# WMR_Sheet.net
KiCad netlist of a schematic drawn in Altium Designer
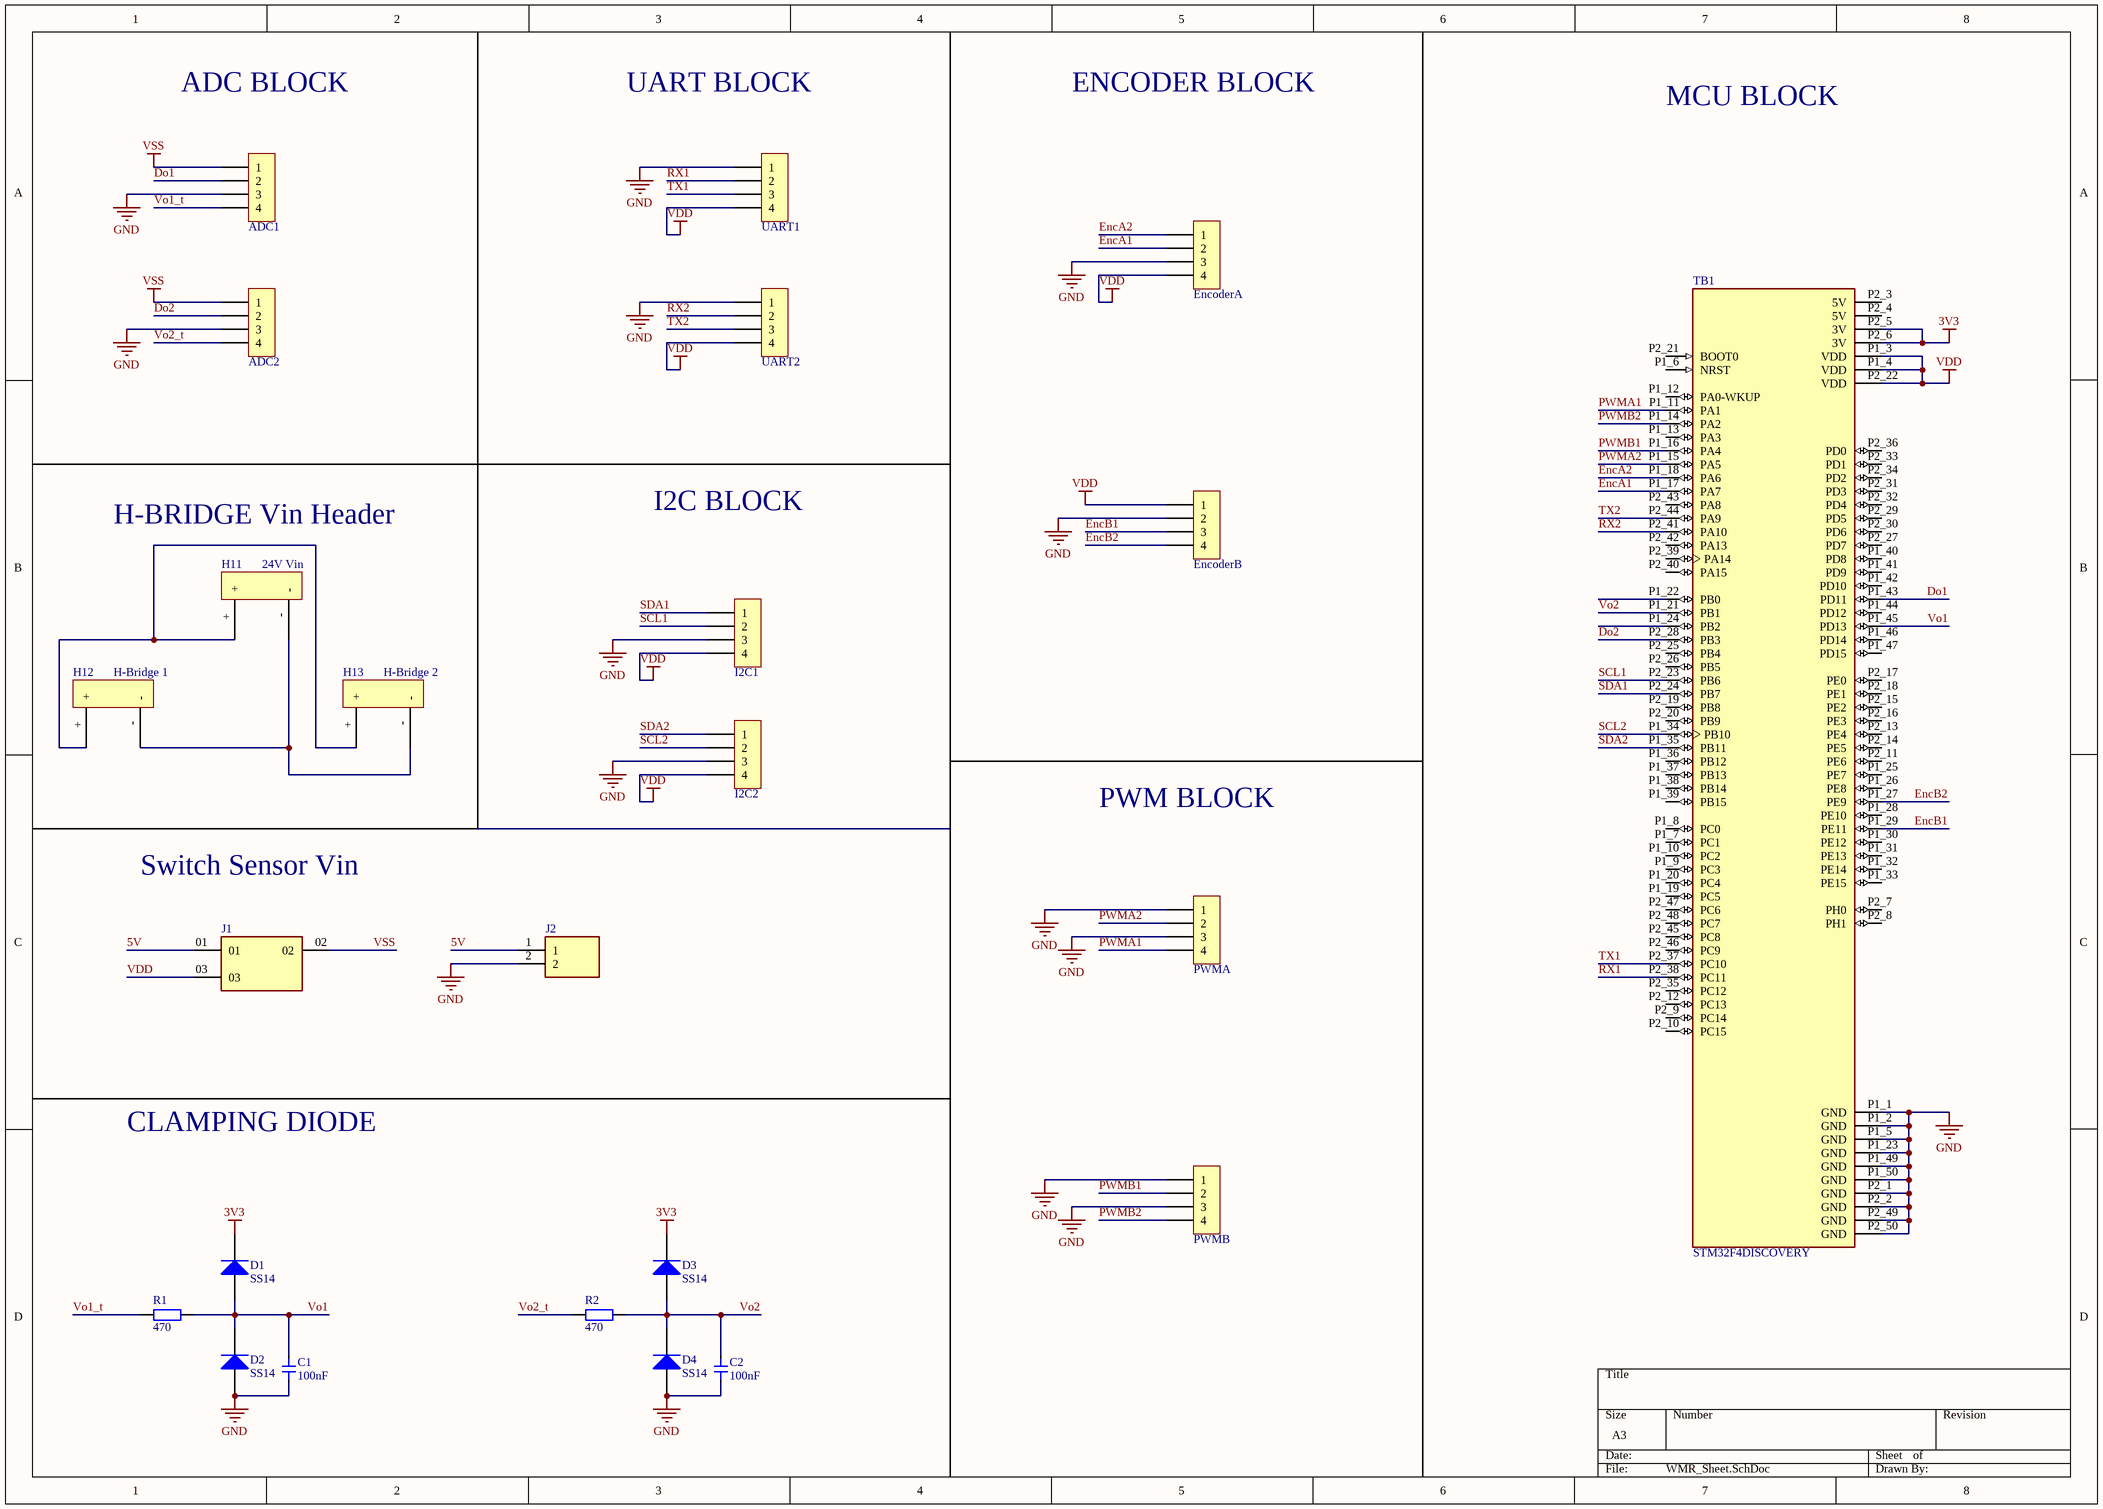
[diagram p0: WMR_Sheet.SchDoc]

(export (version "E")
  (design (tool "Eeschema 10.0.6"))
  (components
    (comp (ref "C1")
      (value "100nF")
      (footprint "Cap 1206")
      (description "Capacitor SMD 1206")
      (libsource (lib "Altium_Lib_by_KhueNguyenCreator") (part "Cap 1206"))
    )
    (comp (ref "C2")
      (value "100nF")
      (footprint "Cap 1206")
      (description "Capacitor SMD 1206")
      (libsource (lib "Altium_Lib_by_KhueNguyenCreator") (part "Cap 1206"))
    )
    (comp (ref "D1")
      (value "SS14")
      (footprint "DIODE SMA")
      (description "Dán")
      (libsource (lib "Altium_Lib_by_KhueNguyenCreator") (part "Diode SS14 ( 1N5819)"))
    )
    (comp (ref "D2")
      (value "SS14")
      (footprint "DIODE SMA")
      (description "Dán")
      (libsource (lib "Altium_Lib_by_KhueNguyenCreator") (part "Diode SS14 ( 1N5819)"))
    )
    (comp (ref "D3")
      (value "SS14")
      (footprint "DIODE SMA")
      (description "Dán")
      (libsource (lib "Altium_Lib_by_KhueNguyenCreator") (part "Diode SS14 ( 1N5819)"))
    )
    (comp (ref "D4")
      (value "SS14")
      (footprint "DIODE SMA")
      (description "Dán")
      (libsource (lib "Altium_Lib_by_KhueNguyenCreator") (part "Diode SS14 ( 1N5819)"))
    )
    (comp (ref "H1")
      (value "EncoderA")
      (footprint "XH2.54M-4")
      (description "Cắm")
      (libsource (lib "Altium_Lib_by_KhueNguyenCreator") (part "Header 4P 2.54 Duc Thang"))
    )
    (comp (ref "H2")
      (value "EncoderB")
      (footprint "XH2.54M-4")
      (description "Cắm")
      (libsource (lib "Altium_Lib_by_KhueNguyenCreator") (part "Header 4P 2.54 Duc Thang"))
    )
    (comp (ref "H3")
      (value "PWMA")
      (footprint "XH2.54M-4")
      (description "Cắm")
      (libsource (lib "Altium_Lib_by_KhueNguyenCreator") (part "Header 4P 2.54 Duc Thang"))
    )
    (comp (ref "H4")
      (value "PWMB")
      (footprint "XH2.54M-4")
      (description "Cắm")
      (libsource (lib "Altium_Lib_by_KhueNguyenCreator") (part "Header 4P 2.54 Duc Thang"))
    )
    (comp (ref "H5")
      (value "UART1")
      (footprint "XH2.54M-4")
      (description "Cắm")
      (libsource (lib "Altium_Lib_by_KhueNguyenCreator") (part "Header 4P 2.54 Duc Thang"))
    )
    (comp (ref "H6")
      (value "UART2")
      (footprint "XH2.54M-4")
      (description "Cắm")
      (libsource (lib "Altium_Lib_by_KhueNguyenCreator") (part "Header 4P 2.54 Duc Thang"))
    )
    (comp (ref "H7")
      (value "I2C1")
      (footprint "XH2.54M-4")
      (description "Cắm")
      (libsource (lib "Altium_Lib_by_KhueNguyenCreator") (part "Header 4P 2.54 Duc Thang"))
    )
    (comp (ref "H8")
      (value "I2C2")
      (footprint "XH2.54M-4")
      (description "Cắm")
      (libsource (lib "Altium_Lib_by_KhueNguyenCreator") (part "Header 4P 2.54 Duc Thang"))
    )
    (comp (ref "H9")
      (value "ADC1")
      (footprint "XH2.54M-4")
      (description "Cắm")
      (libsource (lib "Altium_Lib_by_KhueNguyenCreator") (part "Header 4P 2.54 Duc Thang"))
    )
    (comp (ref "H10")
      (value "ADC2")
      (footprint "XH2.54M-4")
      (description "Cắm")
      (libsource (lib "Altium_Lib_by_KhueNguyenCreator") (part "Header 4P 2.54 Duc Thang"))
    )
    (comp (ref "H11")
      (value "24V Vin")
      (footprint "barrier_terminal")
      (libsource (lib "BaoNguyenLib") (part "Barrier Terminal"))
    )
    (comp (ref "H12")
      (value "H-Bridge 1")
      (footprint "barrier_terminal")
      (libsource (lib "BaoNguyenLib") (part "Barrier Terminal"))
    )
    (comp (ref "H13")
      (value "H-Bridge 2")
      (footprint "barrier_terminal")
      (libsource (lib "BaoNguyenLib") (part "Barrier Terminal"))
    )
    (comp (ref "J1")
      (value "~")
      (footprint "SAMTEC_TSW-101-07-G-T-LL")
      (fields (field (name "MP") "TSW-101-07-G-T-LL"))
      (libsource (lib "Header3Pin") (part "TSW-101-07-G-T-LL"))
    )
    (comp (ref "J2")
      (value "~")
      (footprint "MULTICOMP_MC000048")
      (fields (field (name "MF") "Multicomp") (field (name "MP") "MC000048"))
      (libsource (lib "terminal2P") (part "MC000048"))
    )
    (comp (ref "R1")
      (value "470")
      (footprint "tro smd 1206")
      (description "Dán")
      (libsource (lib "Altium_Lib_by_KhueNguyenCreator") (part "Tro 1206 1% 470k"))
    )
    (comp (ref "R2")
      (value "470")
      (footprint "tro smd 1206")
      (description "Dán")
      (libsource (lib "Altium_Lib_by_KhueNguyenCreator") (part "Tro 1206 1% 470k"))
    )
    (comp (ref "TB1")
      (value "STM32F4DISCOVERY")
      (footprint "MODULE_STM32F4DISCOVERY")
      (description "Development kit: ARM ST; pin strips, pin header; No.of")
      (libsource (lib "STM32F4DISCOVERY") (part "STM32F4DISCOVERY"))
    )
  )
  (nets
    (net (code "1") (name "/5V") (class "Default")
      (node (ref "J1") (pin "01") (pinfunction "01_01") (pintype "passive"))
      (node (ref "J2") (pin "1") (pinfunction "1_1") (pintype "passive"))
    )
    (net (code "2") (name "/Do1") (class "Default")
      (node (ref "H9") (pin "2") (pinfunction "2_2") (pintype "passive"))
      (node (ref "TB1") (pin "P1_43") (pinfunction "PD11_P1_43") (pintype "bidirectional"))
    )
    (net (code "3") (name "/Do2") (class "Default")
      (node (ref "H10") (pin "2") (pinfunction "2_2") (pintype "passive"))
      (node (ref "TB1") (pin "P2_28") (pinfunction "PB3_P2_28") (pintype "bidirectional"))
    )
    (net (code "4") (name "/EncA1") (class "Default")
      (node (ref "H1") (pin "2") (pinfunction "2_2") (pintype "passive"))
      (node (ref "TB1") (pin "P1_17") (pinfunction "PA7_P1_17") (pintype "bidirectional"))
    )
    (net (code "5") (name "/EncA2") (class "Default")
      (node (ref "H1") (pin "1") (pinfunction "1_1") (pintype "passive"))
      (node (ref "TB1") (pin "P1_18") (pinfunction "PA6_P1_18") (pintype "bidirectional"))
    )
    (net (code "6") (name "/EncB1") (class "Default")
      (node (ref "H2") (pin "3") (pinfunction "3_3") (pintype "passive"))
      (node (ref "TB1") (pin "P1_29") (pinfunction "PE11_P1_29") (pintype "bidirectional"))
    )
    (net (code "7") (name "/EncB2") (class "Default")
      (node (ref "H2") (pin "4") (pinfunction "4_4") (pintype "passive"))
      (node (ref "TB1") (pin "P1_27") (pinfunction "PE9_P1_27") (pintype "bidirectional"))
    )
    (net (code "8") (name "/PWMA1") (class "Default")
      (node (ref "H3") (pin "4") (pinfunction "4_4") (pintype "passive"))
      (node (ref "TB1") (pin "P1_11") (pinfunction "PA1_P1_11") (pintype "bidirectional"))
    )
    (net (code "9") (name "/PWMA2") (class "Default")
      (node (ref "H3") (pin "2") (pinfunction "2_2") (pintype "passive"))
      (node (ref "TB1") (pin "P1_15") (pinfunction "PA5_P1_15") (pintype "bidirectional"))
    )
    (net (code "10") (name "/PWMB1") (class "Default")
      (node (ref "H4") (pin "2") (pinfunction "2_2") (pintype "passive"))
      (node (ref "TB1") (pin "P1_16") (pinfunction "PA4_P1_16") (pintype "bidirectional"))
    )
    (net (code "11") (name "/PWMB2") (class "Default")
      (node (ref "H4") (pin "4") (pinfunction "4_4") (pintype "passive"))
      (node (ref "TB1") (pin "P1_14") (pinfunction "PA2_P1_14") (pintype "bidirectional"))
    )
    (net (code "12") (name "/RX1") (class "Default")
      (node (ref "H5") (pin "2") (pinfunction "2_2") (pintype "passive"))
      (node (ref "TB1") (pin "P2_38") (pinfunction "PC11_P2_38") (pintype "bidirectional"))
    )
    (net (code "13") (name "/RX2") (class "Default")
      (node (ref "H6") (pin "2") (pinfunction "2_2") (pintype "passive"))
      (node (ref "TB1") (pin "P2_41") (pinfunction "PA10_P2_41") (pintype "bidirectional"))
    )
    (net (code "14") (name "/SCL1") (class "Default")
      (node (ref "H7") (pin "2") (pinfunction "2_2") (pintype "passive"))
      (node (ref "TB1") (pin "P2_23") (pinfunction "PB6_P2_23") (pintype "bidirectional"))
    )
    (net (code "15") (name "/SCL2") (class "Default")
      (node (ref "H8") (pin "2") (pinfunction "2_2") (pintype "passive"))
      (node (ref "TB1") (pin "P1_34") (pinfunction "PB10_P1_34") (pintype "bidirectional"))
    )
    (net (code "16") (name "/SDA1") (class "Default")
      (node (ref "H7") (pin "1") (pinfunction "1_1") (pintype "passive"))
      (node (ref "TB1") (pin "P2_24") (pinfunction "PB7_P2_24") (pintype "bidirectional"))
    )
    (net (code "17") (name "/SDA2") (class "Default")
      (node (ref "H8") (pin "1") (pinfunction "1_1") (pintype "passive"))
      (node (ref "TB1") (pin "P1_35") (pinfunction "PB11_P1_35") (pintype "bidirectional"))
    )
    (net (code "18") (name "/TX1") (class "Default")
      (node (ref "H5") (pin "3") (pinfunction "3_3") (pintype "passive"))
      (node (ref "TB1") (pin "P2_37") (pinfunction "PC10_P2_37") (pintype "bidirectional"))
    )
    (net (code "19") (name "/TX2") (class "Default")
      (node (ref "H6") (pin "3") (pinfunction "3_3") (pintype "passive"))
      (node (ref "TB1") (pin "P2_44") (pinfunction "PA9_P2_44") (pintype "bidirectional"))
    )
    (net (code "20") (name "/Vo1") (class "Default")
      (node (ref "C1") (pin "1") (pinfunction "1_1") (pintype "passive"))
      (node (ref "D1") (pin "1") (pinfunction "A_1") (pintype "passive"))
      (node (ref "D2") (pin "2") (pinfunction "K_2") (pintype "passive"))
      (node (ref "R1") (pin "2") (pinfunction "2_2") (pintype "passive"))
      (node (ref "TB1") (pin "P1_45") (pinfunction "PD13_P1_45") (pintype "bidirectional"))
    )
    (net (code "21") (name "/Vo1_t") (class "Default")
      (node (ref "H9") (pin "4") (pinfunction "4_4") (pintype "passive"))
      (node (ref "R1") (pin "1") (pinfunction "1_1") (pintype "passive"))
    )
    (net (code "22") (name "/Vo2") (class "Default")
      (node (ref "C2") (pin "1") (pinfunction "1_1") (pintype "passive"))
      (node (ref "D3") (pin "1") (pinfunction "A_1") (pintype "passive"))
      (node (ref "D4") (pin "2") (pinfunction "K_2") (pintype "passive"))
      (node (ref "R2") (pin "2") (pinfunction "2_2") (pintype "passive"))
      (node (ref "TB1") (pin "P1_21") (pinfunction "PB1_P1_21") (pintype "bidirectional"))
    )
    (net (code "23") (name "/Vo2_t") (class "Default")
      (node (ref "H10") (pin "4") (pinfunction "4_4") (pintype "passive"))
      (node (ref "R2") (pin "1") (pinfunction "1_1") (pintype "passive"))
    )
    (net (code "24") (name "3V3") (class "Default")
      (node (ref "D1") (pin "2") (pinfunction "K_2") (pintype "passive"))
      (node (ref "D3") (pin "2") (pinfunction "K_2") (pintype "passive"))
      (node (ref "TB1") (pin "P2_5") (pinfunction "3V_P2_5") (pintype "power_in"))
      (node (ref "TB1") (pin "P2_6") (pinfunction "3V_P2_6") (pintype "power_in"))
    )
    (net (code "25") (name "GND") (class "Default")
      (node (ref "C1") (pin "2") (pinfunction "2_2") (pintype "passive"))
      (node (ref "C2") (pin "2") (pinfunction "2_2") (pintype "passive"))
      (node (ref "D2") (pin "1") (pinfunction "A_1") (pintype "passive"))
      (node (ref "D4") (pin "1") (pinfunction "A_1") (pintype "passive"))
      (node (ref "H1") (pin "3") (pinfunction "3_3") (pintype "passive"))
      (node (ref "H10") (pin "3") (pinfunction "3_3") (pintype "passive"))
      (node (ref "H2") (pin "2") (pinfunction "2_2") (pintype "passive"))
      (node (ref "H3") (pin "1") (pinfunction "1_1") (pintype "passive"))
      (node (ref "H3") (pin "3") (pinfunction "3_3") (pintype "passive"))
      (node (ref "H4") (pin "1") (pinfunction "1_1") (pintype "passive"))
      (node (ref "H4") (pin "3") (pinfunction "3_3") (pintype "passive"))
      (node (ref "H5") (pin "1") (pinfunction "1_1") (pintype "passive"))
      (node (ref "H6") (pin "1") (pinfunction "1_1") (pintype "passive"))
      (node (ref "H7") (pin "3") (pinfunction "3_3") (pintype "passive"))
      (node (ref "H8") (pin "3") (pinfunction "3_3") (pintype "passive"))
      (node (ref "H9") (pin "3") (pinfunction "3_3") (pintype "passive"))
      (node (ref "J2") (pin "2") (pinfunction "2_2") (pintype "passive"))
      (node (ref "TB1") (pin "P1_1") (pinfunction "GND_P1_1") (pintype "power_in"))
      (node (ref "TB1") (pin "P1_2") (pinfunction "GND_P1_2") (pintype "power_in"))
      (node (ref "TB1") (pin "P1_23") (pinfunction "GND_P1_23") (pintype "power_in"))
      (node (ref "TB1") (pin "P1_49") (pinfunction "GND_P1_49") (pintype "power_in"))
      (node (ref "TB1") (pin "P1_5") (pinfunction "GND_P1_5") (pintype "power_in"))
      (node (ref "TB1") (pin "P1_50") (pinfunction "GND_P1_50") (pintype "power_in"))
      (node (ref "TB1") (pin "P2_1") (pinfunction "GND_P2_1") (pintype "power_in"))
      (node (ref "TB1") (pin "P2_2") (pinfunction "GND_P2_2") (pintype "power_in"))
      (node (ref "TB1") (pin "P2_49") (pinfunction "GND_P2_49") (pintype "power_in"))
      (node (ref "TB1") (pin "P2_50") (pinfunction "GND_P2_50") (pintype "power_in"))
    )
    (net (code "26") (name "Net-(H11-Pad+)") (class "Default")
      (node (ref "H11") (pin "+") (pinfunction "+_+") (pintype "passive"))
      (node (ref "H12") (pin "+") (pinfunction "+_+") (pintype "passive"))
      (node (ref "H13") (pin "+") (pinfunction "+_+") (pintype "passive"))
    )
    (net (code "27") (name "Net-(H11-Pad-)") (class "Default")
      (node (ref "H11") (pin "-") (pinfunction "-_-") (pintype "passive"))
      (node (ref "H12") (pin "-") (pinfunction "-_-") (pintype "passive"))
      (node (ref "H13") (pin "-") (pinfunction "-_-") (pintype "passive"))
    )
    (net (code "28") (name "VDD") (class "Default")
      (node (ref "H1") (pin "4") (pinfunction "4_4") (pintype "passive"))
      (node (ref "H2") (pin "1") (pinfunction "1_1") (pintype "passive"))
      (node (ref "H5") (pin "4") (pinfunction "4_4") (pintype "passive"))
      (node (ref "H6") (pin "4") (pinfunction "4_4") (pintype "passive"))
      (node (ref "H7") (pin "4") (pinfunction "4_4") (pintype "passive"))
      (node (ref "H8") (pin "4") (pinfunction "4_4") (pintype "passive"))
      (node (ref "J1") (pin "03") (pinfunction "03_03") (pintype "passive"))
      (node (ref "TB1") (pin "P1_3") (pinfunction "VDD_P1_3") (pintype "power_in"))
      (node (ref "TB1") (pin "P1_4") (pinfunction "VDD_P1_4") (pintype "power_in"))
      (node (ref "TB1") (pin "P2_22") (pinfunction "VDD_P2_22") (pintype "power_in"))
    )
    (net (code "29") (name "VSS") (class "Default")
      (node (ref "H10") (pin "1") (pinfunction "1_1") (pintype "passive"))
      (node (ref "H9") (pin "1") (pinfunction "1_1") (pintype "passive"))
      (node (ref "J1") (pin "02") (pinfunction "02_02") (pintype "passive"))
    )
    (net (code "30") (name "unconnected-(TB1-5V-PadP2_3)") (class "Default")
      (node (ref "TB1") (pin "P2_3") (pinfunction "5V_P2_3") (pintype "power_in"))
    )
    (net (code "31") (name "unconnected-(TB1-5V-PadP2_4)") (class "Default")
      (node (ref "TB1") (pin "P2_4") (pinfunction "5V_P2_4") (pintype "power_in"))
    )
    (net (code "32") (name "unconnected-(TB1-BOOT0-PadP2_21)") (class "Default")
      (node (ref "TB1") (pin "P2_21") (pinfunction "BOOT0_P2_21") (pintype "input"))
    )
    (net (code "33") (name "unconnected-(TB1-NRST-PadP1_6)") (class "Default")
      (node (ref "TB1") (pin "P1_6") (pinfunction "NRST_P1_6") (pintype "input"))
    )
    (net (code "34") (name "unconnected-(TB1-PA0-WKUP-PadP1_12)") (class "Default")
      (node (ref "TB1") (pin "P1_12") (pinfunction "PA0-WKUP_P1_12") (pintype "bidirectional"))
    )
    (net (code "35") (name "unconnected-(TB1-PA3-PadP1_13)") (class "Default")
      (node (ref "TB1") (pin "P1_13") (pinfunction "PA3_P1_13") (pintype "bidirectional"))
    )
    (net (code "36") (name "unconnected-(TB1-PA8-PadP2_43)") (class "Default")
      (node (ref "TB1") (pin "P2_43") (pinfunction "PA8_P2_43") (pintype "bidirectional"))
    )
    (net (code "37") (name "unconnected-(TB1-PA13-PadP2_42)") (class "Default")
      (node (ref "TB1") (pin "P2_42") (pinfunction "PA13_P2_42") (pintype "bidirectional"))
    )
    (net (code "38") (name "unconnected-(TB1-PA14-PadP2_39)") (class "Default")
      (node (ref "TB1") (pin "P2_39") (pinfunction "PA14_P2_39") (pintype "bidirectional"))
    )
    (net (code "39") (name "unconnected-(TB1-PA15-PadP2_40)") (class "Default")
      (node (ref "TB1") (pin "P2_40") (pinfunction "PA15_P2_40") (pintype "bidirectional"))
    )
    (net (code "40") (name "unconnected-(TB1-PB0-PadP1_22)") (class "Default")
      (node (ref "TB1") (pin "P1_22") (pinfunction "PB0_P1_22") (pintype "bidirectional"))
    )
    (net (code "41") (name "unconnected-(TB1-PB2-PadP1_24)") (class "Default")
      (node (ref "TB1") (pin "P1_24") (pinfunction "PB2_P1_24") (pintype "bidirectional"))
    )
    (net (code "42") (name "unconnected-(TB1-PB4-PadP2_25)") (class "Default")
      (node (ref "TB1") (pin "P2_25") (pinfunction "PB4_P2_25") (pintype "bidirectional"))
    )
    (net (code "43") (name "unconnected-(TB1-PB5-PadP2_26)") (class "Default")
      (node (ref "TB1") (pin "P2_26") (pinfunction "PB5_P2_26") (pintype "bidirectional"))
    )
    (net (code "44") (name "unconnected-(TB1-PB8-PadP2_19)") (class "Default")
      (node (ref "TB1") (pin "P2_19") (pinfunction "PB8_P2_19") (pintype "bidirectional"))
    )
    (net (code "45") (name "unconnected-(TB1-PB9-PadP2_20)") (class "Default")
      (node (ref "TB1") (pin "P2_20") (pinfunction "PB9_P2_20") (pintype "bidirectional"))
    )
    (net (code "46") (name "unconnected-(TB1-PB12-PadP1_36)") (class "Default")
      (node (ref "TB1") (pin "P1_36") (pinfunction "PB12_P1_36") (pintype "bidirectional"))
    )
    (net (code "47") (name "unconnected-(TB1-PB13-PadP1_37)") (class "Default")
      (node (ref "TB1") (pin "P1_37") (pinfunction "PB13_P1_37") (pintype "bidirectional"))
    )
    (net (code "48") (name "unconnected-(TB1-PB14-PadP1_38)") (class "Default")
      (node (ref "TB1") (pin "P1_38") (pinfunction "PB14_P1_38") (pintype "bidirectional"))
    )
    (net (code "49") (name "unconnected-(TB1-PB15-PadP1_39)") (class "Default")
      (node (ref "TB1") (pin "P1_39") (pinfunction "PB15_P1_39") (pintype "bidirectional"))
    )
    (net (code "50") (name "unconnected-(TB1-PC0-PadP1_8)") (class "Default")
      (node (ref "TB1") (pin "P1_8") (pinfunction "PC0_P1_8") (pintype "bidirectional"))
    )
    (net (code "51") (name "unconnected-(TB1-PC1-PadP1_7)") (class "Default")
      (node (ref "TB1") (pin "P1_7") (pinfunction "PC1_P1_7") (pintype "bidirectional"))
    )
    (net (code "52") (name "unconnected-(TB1-PC2-PadP1_10)") (class "Default")
      (node (ref "TB1") (pin "P1_10") (pinfunction "PC2_P1_10") (pintype "bidirectional"))
    )
    (net (code "53") (name "unconnected-(TB1-PC3-PadP1_9)") (class "Default")
      (node (ref "TB1") (pin "P1_9") (pinfunction "PC3_P1_9") (pintype "bidirectional"))
    )
    (net (code "54") (name "unconnected-(TB1-PC4-PadP1_20)") (class "Default")
      (node (ref "TB1") (pin "P1_20") (pinfunction "PC4_P1_20") (pintype "bidirectional"))
    )
    (net (code "55") (name "unconnected-(TB1-PC5-PadP1_19)") (class "Default")
      (node (ref "TB1") (pin "P1_19") (pinfunction "PC5_P1_19") (pintype "bidirectional"))
    )
    (net (code "56") (name "unconnected-(TB1-PC6-PadP2_47)") (class "Default")
      (node (ref "TB1") (pin "P2_47") (pinfunction "PC6_P2_47") (pintype "bidirectional"))
    )
    (net (code "57") (name "unconnected-(TB1-PC7-PadP2_48)") (class "Default")
      (node (ref "TB1") (pin "P2_48") (pinfunction "PC7_P2_48") (pintype "bidirectional"))
    )
    (net (code "58") (name "unconnected-(TB1-PC8-PadP2_45)") (class "Default")
      (node (ref "TB1") (pin "P2_45") (pinfunction "PC8_P2_45") (pintype "bidirectional"))
    )
    (net (code "59") (name "unconnected-(TB1-PC9-PadP2_46)") (class "Default")
      (node (ref "TB1") (pin "P2_46") (pinfunction "PC9_P2_46") (pintype "bidirectional"))
    )
    (net (code "60") (name "unconnected-(TB1-PC12-PadP2_35)") (class "Default")
      (node (ref "TB1") (pin "P2_35") (pinfunction "PC12_P2_35") (pintype "bidirectional"))
    )
    (net (code "61") (name "unconnected-(TB1-PC13-PadP2_12)") (class "Default")
      (node (ref "TB1") (pin "P2_12") (pinfunction "PC13_P2_12") (pintype "bidirectional"))
    )
    (net (code "62") (name "unconnected-(TB1-PC14-PadP2_9)") (class "Default")
      (node (ref "TB1") (pin "P2_9") (pinfunction "PC14_P2_9") (pintype "bidirectional"))
    )
    (net (code "63") (name "unconnected-(TB1-PC15-PadP2_10)") (class "Default")
      (node (ref "TB1") (pin "P2_10") (pinfunction "PC15_P2_10") (pintype "bidirectional"))
    )
    (net (code "64") (name "unconnected-(TB1-PD0-PadP2_36)") (class "Default")
      (node (ref "TB1") (pin "P2_36") (pinfunction "PD0_P2_36") (pintype "bidirectional"))
    )
    (net (code "65") (name "unconnected-(TB1-PD1-PadP2_33)") (class "Default")
      (node (ref "TB1") (pin "P2_33") (pinfunction "PD1_P2_33") (pintype "bidirectional"))
    )
    (net (code "66") (name "unconnected-(TB1-PD2-PadP2_34)") (class "Default")
      (node (ref "TB1") (pin "P2_34") (pinfunction "PD2_P2_34") (pintype "bidirectional"))
    )
    (net (code "67") (name "unconnected-(TB1-PD3-PadP2_31)") (class "Default")
      (node (ref "TB1") (pin "P2_31") (pinfunction "PD3_P2_31") (pintype "bidirectional"))
    )
    (net (code "68") (name "unconnected-(TB1-PD4-PadP2_32)") (class "Default")
      (node (ref "TB1") (pin "P2_32") (pinfunction "PD4_P2_32") (pintype "bidirectional"))
    )
    (net (code "69") (name "unconnected-(TB1-PD5-PadP2_29)") (class "Default")
      (node (ref "TB1") (pin "P2_29") (pinfunction "PD5_P2_29") (pintype "bidirectional"))
    )
    (net (code "70") (name "unconnected-(TB1-PD6-PadP2_30)") (class "Default")
      (node (ref "TB1") (pin "P2_30") (pinfunction "PD6_P2_30") (pintype "bidirectional"))
    )
    (net (code "71") (name "unconnected-(TB1-PD7-PadP2_27)") (class "Default")
      (node (ref "TB1") (pin "P2_27") (pinfunction "PD7_P2_27") (pintype "bidirectional"))
    )
    (net (code "72") (name "unconnected-(TB1-PD8-PadP1_40)") (class "Default")
      (node (ref "TB1") (pin "P1_40") (pinfunction "PD8_P1_40") (pintype "bidirectional"))
    )
    (net (code "73") (name "unconnected-(TB1-PD9-PadP1_41)") (class "Default")
      (node (ref "TB1") (pin "P1_41") (pinfunction "PD9_P1_41") (pintype "bidirectional"))
    )
    (net (code "74") (name "unconnected-(TB1-PD10-PadP1_42)") (class "Default")
      (node (ref "TB1") (pin "P1_42") (pinfunction "PD10_P1_42") (pintype "bidirectional"))
    )
    (net (code "75") (name "unconnected-(TB1-PD12-PadP1_44)") (class "Default")
      (node (ref "TB1") (pin "P1_44") (pinfunction "PD12_P1_44") (pintype "bidirectional"))
    )
    (net (code "76") (name "unconnected-(TB1-PD14-PadP1_46)") (class "Default")
      (node (ref "TB1") (pin "P1_46") (pinfunction "PD14_P1_46") (pintype "bidirectional"))
    )
    (net (code "77") (name "unconnected-(TB1-PD15-PadP1_47)") (class "Default")
      (node (ref "TB1") (pin "P1_47") (pinfunction "PD15_P1_47") (pintype "bidirectional"))
    )
    (net (code "78") (name "unconnected-(TB1-PE0-PadP2_17)") (class "Default")
      (node (ref "TB1") (pin "P2_17") (pinfunction "PE0_P2_17") (pintype "bidirectional"))
    )
    (net (code "79") (name "unconnected-(TB1-PE1-PadP2_18)") (class "Default")
      (node (ref "TB1") (pin "P2_18") (pinfunction "PE1_P2_18") (pintype "bidirectional"))
    )
    (net (code "80") (name "unconnected-(TB1-PE2-PadP2_15)") (class "Default")
      (node (ref "TB1") (pin "P2_15") (pinfunction "PE2_P2_15") (pintype "bidirectional"))
    )
    (net (code "81") (name "unconnected-(TB1-PE3-PadP2_16)") (class "Default")
      (node (ref "TB1") (pin "P2_16") (pinfunction "PE3_P2_16") (pintype "bidirectional"))
    )
    (net (code "82") (name "unconnected-(TB1-PE4-PadP2_13)") (class "Default")
      (node (ref "TB1") (pin "P2_13") (pinfunction "PE4_P2_13") (pintype "bidirectional"))
    )
    (net (code "83") (name "unconnected-(TB1-PE5-PadP2_14)") (class "Default")
      (node (ref "TB1") (pin "P2_14") (pinfunction "PE5_P2_14") (pintype "bidirectional"))
    )
    (net (code "84") (name "unconnected-(TB1-PE6-PadP2_11)") (class "Default")
      (node (ref "TB1") (pin "P2_11") (pinfunction "PE6_P2_11") (pintype "bidirectional"))
    )
    (net (code "85") (name "unconnected-(TB1-PE7-PadP1_25)") (class "Default")
      (node (ref "TB1") (pin "P1_25") (pinfunction "PE7_P1_25") (pintype "bidirectional"))
    )
    (net (code "86") (name "unconnected-(TB1-PE8-PadP1_26)") (class "Default")
      (node (ref "TB1") (pin "P1_26") (pinfunction "PE8_P1_26") (pintype "bidirectional"))
    )
    (net (code "87") (name "unconnected-(TB1-PE10-PadP1_28)") (class "Default")
      (node (ref "TB1") (pin "P1_28") (pinfunction "PE10_P1_28") (pintype "bidirectional"))
    )
    (net (code "88") (name "unconnected-(TB1-PE12-PadP1_30)") (class "Default")
      (node (ref "TB1") (pin "P1_30") (pinfunction "PE12_P1_30") (pintype "bidirectional"))
    )
    (net (code "89") (name "unconnected-(TB1-PE13-PadP1_31)") (class "Default")
      (node (ref "TB1") (pin "P1_31") (pinfunction "PE13_P1_31") (pintype "bidirectional"))
    )
    (net (code "90") (name "unconnected-(TB1-PE14-PadP1_32)") (class "Default")
      (node (ref "TB1") (pin "P1_32") (pinfunction "PE14_P1_32") (pintype "bidirectional"))
    )
    (net (code "91") (name "unconnected-(TB1-PE15-PadP1_33)") (class "Default")
      (node (ref "TB1") (pin "P1_33") (pinfunction "PE15_P1_33") (pintype "bidirectional"))
    )
    (net (code "92") (name "unconnected-(TB1-PH0-PadP2_7)") (class "Default")
      (node (ref "TB1") (pin "P2_7") (pinfunction "PH0_P2_7") (pintype "bidirectional"))
    )
    (net (code "93") (name "unconnected-(TB1-PH1-PadP2_8)") (class "Default")
      (node (ref "TB1") (pin "P2_8") (pinfunction "PH1_P2_8") (pintype "bidirectional"))
    )
  )
)
